# 2_cyber60-alps_matrix.net
KiCad netlist of a schematic drawn in Altium Designer
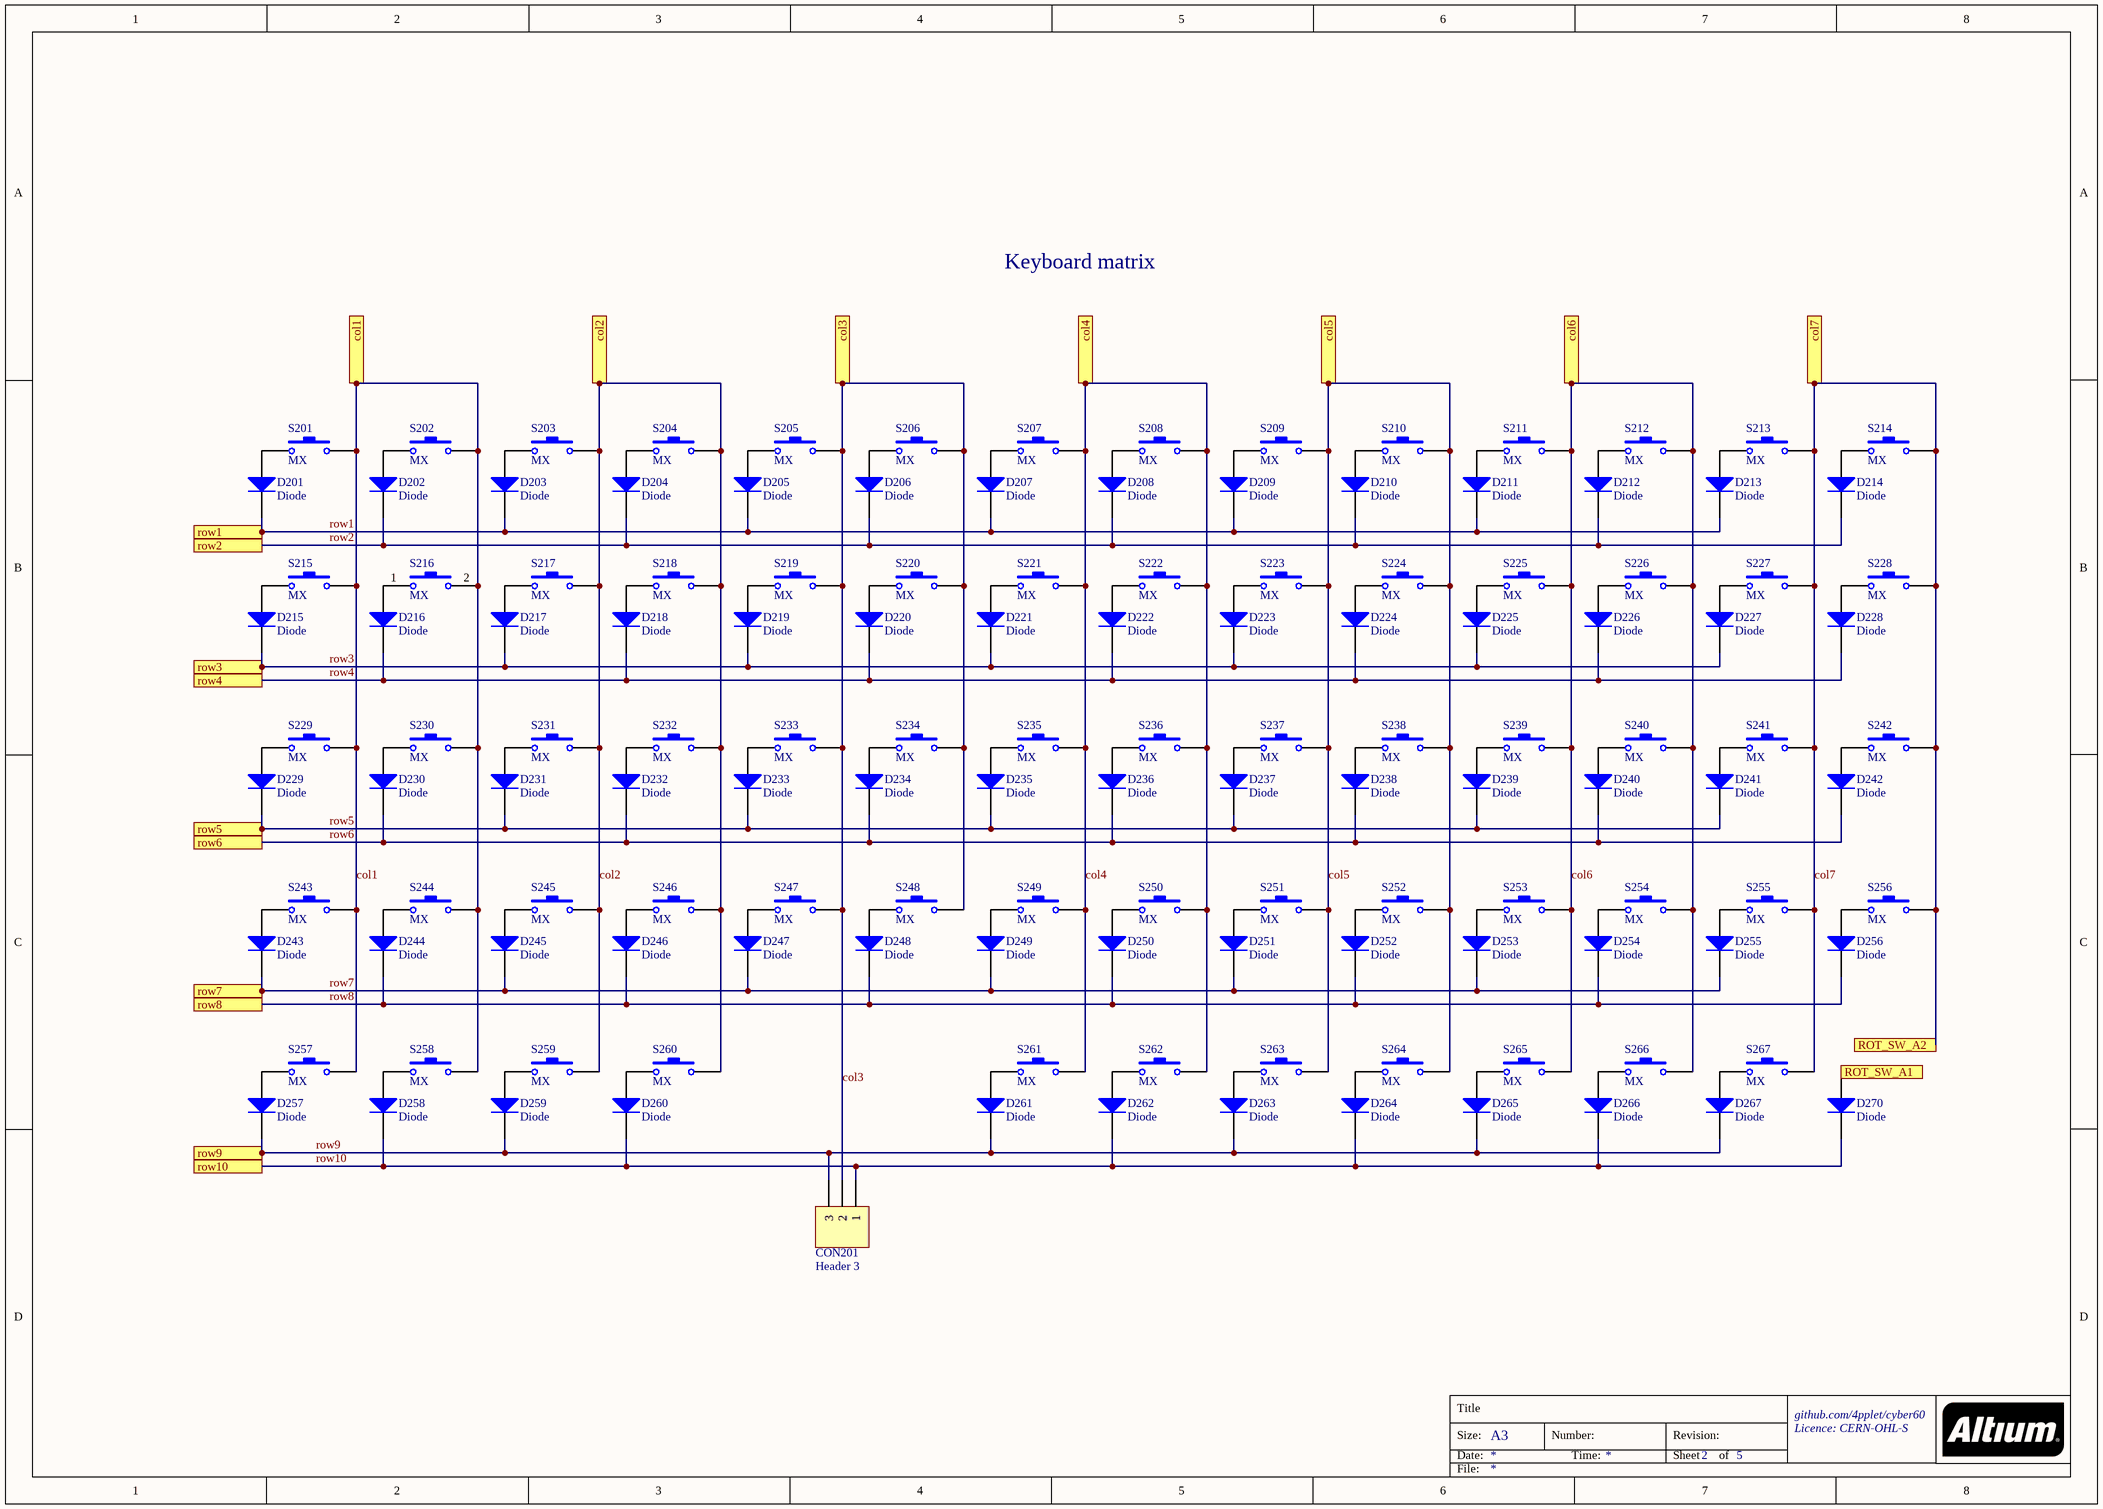
[diagram p0: 2_cyber60-alps_matrix.SchDoc]

(export (version "E")
  (design (tool "Eeschema 10.0.6"))
  (components
    (comp (ref "CON201")
      (value "Header 3")
      (footprint "HDR1X3")
      (description "Header, 3-Pin")
      (libsource (lib "Miscellaneous Connectors") (part "Header 3"))
    )
    (comp (ref "D201")
      (value "Diode")
      (footprint "SOD-123")
      (description "Default Diode")
      (fields (field (name "LCSC PART #") "C81598") (field (name "MRF.PART") "1N4148W"))
      (libsource (lib "Miscellaneous Devices") (part "Diode"))
    )
    (comp (ref "D202")
      (value "Diode")
      (footprint "SOD-123")
      (description "Default Diode")
      (fields (field (name "LCSC PART #") "C81598") (field (name "MRF.PART") "1N4148W"))
      (libsource (lib "Miscellaneous Devices") (part "Diode"))
    )
    (comp (ref "D203")
      (value "Diode")
      (footprint "SOD-123")
      (description "Default Diode")
      (fields (field (name "LCSC PART #") "C81598") (field (name "MRF.PART") "1N4148W"))
      (libsource (lib "Miscellaneous Devices") (part "Diode"))
    )
    (comp (ref "D204")
      (value "Diode")
      (footprint "SOD-123")
      (description "Default Diode")
      (fields (field (name "LCSC PART #") "C81598") (field (name "MRF.PART") "1N4148W"))
      (libsource (lib "Miscellaneous Devices") (part "Diode"))
    )
    (comp (ref "D205")
      (value "Diode")
      (footprint "SOD-123")
      (description "Default Diode")
      (fields (field (name "LCSC PART #") "C81598") (field (name "MRF.PART") "1N4148W"))
      (libsource (lib "Miscellaneous Devices") (part "Diode"))
    )
    (comp (ref "D206")
      (value "Diode")
      (footprint "SOD-123")
      (description "Default Diode")
      (fields (field (name "LCSC PART #") "C81598") (field (name "MRF.PART") "1N4148W"))
      (libsource (lib "Miscellaneous Devices") (part "Diode"))
    )
    (comp (ref "D207")
      (value "Diode")
      (footprint "SOD-123")
      (description "Default Diode")
      (fields (field (name "LCSC PART #") "C81598") (field (name "MRF.PART") "1N4148W"))
      (libsource (lib "Miscellaneous Devices") (part "Diode"))
    )
    (comp (ref "D208")
      (value "Diode")
      (footprint "SOD-123")
      (description "Default Diode")
      (fields (field (name "LCSC PART #") "C81598") (field (name "MRF.PART") "1N4148W"))
      (libsource (lib "Miscellaneous Devices") (part "Diode"))
    )
    (comp (ref "D209")
      (value "Diode")
      (footprint "SOD-123")
      (description "Default Diode")
      (fields (field (name "LCSC PART #") "C81598") (field (name "MRF.PART") "1N4148W"))
      (libsource (lib "Miscellaneous Devices") (part "Diode"))
    )
    (comp (ref "D210")
      (value "Diode")
      (footprint "SOD-123")
      (description "Default Diode")
      (fields (field (name "LCSC PART #") "C81598") (field (name "MRF.PART") "1N4148W"))
      (libsource (lib "Miscellaneous Devices") (part "Diode"))
    )
    (comp (ref "D211")
      (value "Diode")
      (footprint "SOD-123")
      (description "Default Diode")
      (fields (field (name "LCSC PART #") "C81598") (field (name "MRF.PART") "1N4148W"))
      (libsource (lib "Miscellaneous Devices") (part "Diode"))
    )
    (comp (ref "D212")
      (value "Diode")
      (footprint "SOD-123")
      (description "Default Diode")
      (fields (field (name "LCSC PART #") "C81598") (field (name "MRF.PART") "1N4148W"))
      (libsource (lib "Miscellaneous Devices") (part "Diode"))
    )
    (comp (ref "D213")
      (value "Diode")
      (footprint "SOD-123")
      (description "Default Diode")
      (fields (field (name "LCSC PART #") "C81598") (field (name "MRF.PART") "1N4148W"))
      (libsource (lib "Miscellaneous Devices") (part "Diode"))
    )
    (comp (ref "D214")
      (value "Diode")
      (footprint "SOD-123")
      (description "Default Diode")
      (fields (field (name "LCSC PART #") "C81598") (field (name "MRF.PART") "1N4148W"))
      (libsource (lib "Miscellaneous Devices") (part "Diode"))
    )
    (comp (ref "D215")
      (value "Diode")
      (footprint "SOD-123")
      (description "Default Diode")
      (fields (field (name "LCSC PART #") "C81598") (field (name "MRF.PART") "1N4148W"))
      (libsource (lib "Miscellaneous Devices") (part "Diode"))
    )
    (comp (ref "D216")
      (value "Diode")
      (footprint "SOD-123")
      (description "Default Diode")
      (fields (field (name "LCSC PART #") "C81598") (field (name "MRF.PART") "1N4148W"))
      (libsource (lib "Miscellaneous Devices") (part "Diode"))
    )
    (comp (ref "D217")
      (value "Diode")
      (footprint "SOD-123")
      (description "Default Diode")
      (fields (field (name "LCSC PART #") "C81598") (field (name "MRF.PART") "1N4148W"))
      (libsource (lib "Miscellaneous Devices") (part "Diode"))
    )
    (comp (ref "D218")
      (value "Diode")
      (footprint "SOD-123")
      (description "Default Diode")
      (fields (field (name "LCSC PART #") "C81598") (field (name "MRF.PART") "1N4148W"))
      (libsource (lib "Miscellaneous Devices") (part "Diode"))
    )
    (comp (ref "D219")
      (value "Diode")
      (footprint "SOD-123")
      (description "Default Diode")
      (fields (field (name "LCSC PART #") "C81598") (field (name "MRF.PART") "1N4148W"))
      (libsource (lib "Miscellaneous Devices") (part "Diode"))
    )
    (comp (ref "D220")
      (value "Diode")
      (footprint "SOD-123")
      (description "Default Diode")
      (fields (field (name "LCSC PART #") "C81598") (field (name "MRF.PART") "1N4148W"))
      (libsource (lib "Miscellaneous Devices") (part "Diode"))
    )
    (comp (ref "D221")
      (value "Diode")
      (footprint "SOD-123")
      (description "Default Diode")
      (fields (field (name "LCSC PART #") "C81598") (field (name "MRF.PART") "1N4148W"))
      (libsource (lib "Miscellaneous Devices") (part "Diode"))
    )
    (comp (ref "D222")
      (value "Diode")
      (footprint "SOD-123")
      (description "Default Diode")
      (fields (field (name "LCSC PART #") "C81598") (field (name "MRF.PART") "1N4148W"))
      (libsource (lib "Miscellaneous Devices") (part "Diode"))
    )
    (comp (ref "D223")
      (value "Diode")
      (footprint "SOD-123")
      (description "Default Diode")
      (fields (field (name "LCSC PART #") "C81598") (field (name "MRF.PART") "1N4148W"))
      (libsource (lib "Miscellaneous Devices") (part "Diode"))
    )
    (comp (ref "D224")
      (value "Diode")
      (footprint "SOD-123")
      (description "Default Diode")
      (fields (field (name "LCSC PART #") "C81598") (field (name "MRF.PART") "1N4148W"))
      (libsource (lib "Miscellaneous Devices") (part "Diode"))
    )
    (comp (ref "D225")
      (value "Diode")
      (footprint "SOD-123")
      (description "Default Diode")
      (fields (field (name "LCSC PART #") "C81598") (field (name "MRF.PART") "1N4148W"))
      (libsource (lib "Miscellaneous Devices") (part "Diode"))
    )
    (comp (ref "D226")
      (value "Diode")
      (footprint "SOD-123")
      (description "Default Diode")
      (fields (field (name "LCSC PART #") "C81598") (field (name "MRF.PART") "1N4148W"))
      (libsource (lib "Miscellaneous Devices") (part "Diode"))
    )
    (comp (ref "D227")
      (value "Diode")
      (footprint "SOD-123")
      (description "Default Diode")
      (fields (field (name "LCSC PART #") "C81598") (field (name "MRF.PART") "1N4148W"))
      (libsource (lib "Miscellaneous Devices") (part "Diode"))
    )
    (comp (ref "D228")
      (value "Diode")
      (footprint "SOD-123")
      (description "Default Diode")
      (fields (field (name "LCSC PART #") "C81598") (field (name "MRF.PART") "1N4148W"))
      (libsource (lib "Miscellaneous Devices") (part "Diode"))
    )
    (comp (ref "D229")
      (value "Diode")
      (footprint "SOD-123")
      (description "Default Diode")
      (fields (field (name "LCSC PART #") "C81598") (field (name "MRF.PART") "1N4148W"))
      (libsource (lib "Miscellaneous Devices") (part "Diode"))
    )
    (comp (ref "D230")
      (value "Diode")
      (footprint "SOD-123")
      (description "Default Diode")
      (fields (field (name "LCSC PART #") "C81598") (field (name "MRF.PART") "1N4148W"))
      (libsource (lib "Miscellaneous Devices") (part "Diode"))
    )
    (comp (ref "D231")
      (value "Diode")
      (footprint "SOD-123")
      (description "Default Diode")
      (fields (field (name "LCSC PART #") "C81598") (field (name "MRF.PART") "1N4148W"))
      (libsource (lib "Miscellaneous Devices") (part "Diode"))
    )
    (comp (ref "D232")
      (value "Diode")
      (footprint "SOD-123")
      (description "Default Diode")
      (fields (field (name "LCSC PART #") "C81598") (field (name "MRF.PART") "1N4148W"))
      (libsource (lib "Miscellaneous Devices") (part "Diode"))
    )
    (comp (ref "D233")
      (value "Diode")
      (footprint "SOD-123")
      (description "Default Diode")
      (fields (field (name "LCSC PART #") "C81598") (field (name "MRF.PART") "1N4148W"))
      (libsource (lib "Miscellaneous Devices") (part "Diode"))
    )
    (comp (ref "D234")
      (value "Diode")
      (footprint "SOD-123")
      (description "Default Diode")
      (fields (field (name "LCSC PART #") "C81598") (field (name "MRF.PART") "1N4148W"))
      (libsource (lib "Miscellaneous Devices") (part "Diode"))
    )
    (comp (ref "D235")
      (value "Diode")
      (footprint "SOD-123")
      (description "Default Diode")
      (fields (field (name "LCSC PART #") "C81598") (field (name "MRF.PART") "1N4148W"))
      (libsource (lib "Miscellaneous Devices") (part "Diode"))
    )
    (comp (ref "D236")
      (value "Diode")
      (footprint "SOD-123")
      (description "Default Diode")
      (fields (field (name "LCSC PART #") "C81598") (field (name "MRF.PART") "1N4148W"))
      (libsource (lib "Miscellaneous Devices") (part "Diode"))
    )
    (comp (ref "D237")
      (value "Diode")
      (footprint "SOD-123")
      (description "Default Diode")
      (fields (field (name "LCSC PART #") "C81598") (field (name "MRF.PART") "1N4148W"))
      (libsource (lib "Miscellaneous Devices") (part "Diode"))
    )
    (comp (ref "D238")
      (value "Diode")
      (footprint "SOD-123")
      (description "Default Diode")
      (fields (field (name "LCSC PART #") "C81598") (field (name "MRF.PART") "1N4148W"))
      (libsource (lib "Miscellaneous Devices") (part "Diode"))
    )
    (comp (ref "D239")
      (value "Diode")
      (footprint "SOD-123")
      (description "Default Diode")
      (fields (field (name "LCSC PART #") "C81598") (field (name "MRF.PART") "1N4148W"))
      (libsource (lib "Miscellaneous Devices") (part "Diode"))
    )
    (comp (ref "D240")
      (value "Diode")
      (footprint "SOD-123")
      (description "Default Diode")
      (fields (field (name "LCSC PART #") "C81598") (field (name "MRF.PART") "1N4148W"))
      (libsource (lib "Miscellaneous Devices") (part "Diode"))
    )
    (comp (ref "D241")
      (value "Diode")
      (footprint "SOD-123")
      (description "Default Diode")
      (fields (field (name "LCSC PART #") "C81598") (field (name "MRF.PART") "1N4148W"))
      (libsource (lib "Miscellaneous Devices") (part "Diode"))
    )
    (comp (ref "D242")
      (value "Diode")
      (footprint "SOD-123")
      (description "Default Diode")
      (fields (field (name "LCSC PART #") "C81598") (field (name "MRF.PART") "1N4148W"))
      (libsource (lib "Miscellaneous Devices") (part "Diode"))
    )
    (comp (ref "D243")
      (value "Diode")
      (footprint "SOD-123")
      (description "Default Diode")
      (fields (field (name "LCSC PART #") "C81598") (field (name "MRF.PART") "1N4148W"))
      (libsource (lib "Miscellaneous Devices") (part "Diode"))
    )
    (comp (ref "D244")
      (value "Diode")
      (footprint "SOD-123")
      (description "Default Diode")
      (fields (field (name "LCSC PART #") "C81598") (field (name "MRF.PART") "1N4148W"))
      (libsource (lib "Miscellaneous Devices") (part "Diode"))
    )
    (comp (ref "D245")
      (value "Diode")
      (footprint "SOD-123")
      (description "Default Diode")
      (fields (field (name "LCSC PART #") "C81598") (field (name "MRF.PART") "1N4148W"))
      (libsource (lib "Miscellaneous Devices") (part "Diode"))
    )
    (comp (ref "D246")
      (value "Diode")
      (footprint "SOD-123")
      (description "Default Diode")
      (fields (field (name "LCSC PART #") "C81598") (field (name "MRF.PART") "1N4148W"))
      (libsource (lib "Miscellaneous Devices") (part "Diode"))
    )
    (comp (ref "D247")
      (value "Diode")
      (footprint "SOD-123")
      (description "Default Diode")
      (fields (field (name "LCSC PART #") "C81598") (field (name "MRF.PART") "1N4148W"))
      (libsource (lib "Miscellaneous Devices") (part "Diode"))
    )
    (comp (ref "D248")
      (value "Diode")
      (footprint "SOD-123")
      (description "Default Diode")
      (fields (field (name "LCSC PART #") "C81598") (field (name "MRF.PART") "1N4148W"))
      (libsource (lib "Miscellaneous Devices") (part "Diode"))
    )
    (comp (ref "D249")
      (value "Diode")
      (footprint "SOD-123")
      (description "Default Diode")
      (fields (field (name "LCSC PART #") "C81598") (field (name "MRF.PART") "1N4148W"))
      (libsource (lib "Miscellaneous Devices") (part "Diode"))
    )
    (comp (ref "D250")
      (value "Diode")
      (footprint "SOD-123")
      (description "Default Diode")
      (fields (field (name "LCSC PART #") "C81598") (field (name "MRF.PART") "1N4148W"))
      (libsource (lib "Miscellaneous Devices") (part "Diode"))
    )
    (comp (ref "D251")
      (value "Diode")
      (footprint "SOD-123")
      (description "Default Diode")
      (fields (field (name "LCSC PART #") "C81598") (field (name "MRF.PART") "1N4148W"))
      (libsource (lib "Miscellaneous Devices") (part "Diode"))
    )
    (comp (ref "D252")
      (value "Diode")
      (footprint "SOD-123")
      (description "Default Diode")
      (fields (field (name "LCSC PART #") "C81598") (field (name "MRF.PART") "1N4148W"))
      (libsource (lib "Miscellaneous Devices") (part "Diode"))
    )
    (comp (ref "D253")
      (value "Diode")
      (footprint "SOD-123")
      (description "Default Diode")
      (fields (field (name "LCSC PART #") "C81598") (field (name "MRF.PART") "1N4148W"))
      (libsource (lib "Miscellaneous Devices") (part "Diode"))
    )
    (comp (ref "D254")
      (value "Diode")
      (footprint "SOD-123")
      (description "Default Diode")
      (fields (field (name "LCSC PART #") "C81598") (field (name "MRF.PART") "1N4148W"))
      (libsource (lib "Miscellaneous Devices") (part "Diode"))
    )
    (comp (ref "D255")
      (value "Diode")
      (footprint "SOD-123")
      (description "Default Diode")
      (fields (field (name "LCSC PART #") "C81598") (field (name "MRF.PART") "1N4148W"))
      (libsource (lib "Miscellaneous Devices") (part "Diode"))
    )
    (comp (ref "D256")
      (value "Diode")
      (footprint "SOD-123")
      (description "Default Diode")
      (fields (field (name "LCSC PART #") "C81598") (field (name "MRF.PART") "1N4148W"))
      (libsource (lib "Miscellaneous Devices") (part "Diode"))
    )
    (comp (ref "D257")
      (value "Diode")
      (footprint "SOD-123")
      (description "Default Diode")
      (fields (field (name "LCSC PART #") "C81598") (field (name "MRF.PART") "1N4148W"))
      (libsource (lib "Miscellaneous Devices") (part "Diode"))
    )
    (comp (ref "D258")
      (value "Diode")
      (footprint "SOD-123")
      (description "Default Diode")
      (fields (field (name "LCSC PART #") "C81598") (field (name "MRF.PART") "1N4148W"))
      (libsource (lib "Miscellaneous Devices") (part "Diode"))
    )
    (comp (ref "D259")
      (value "Diode")
      (footprint "SOD-123")
      (description "Default Diode")
      (fields (field (name "LCSC PART #") "C81598") (field (name "MRF.PART") "1N4148W"))
      (libsource (lib "Miscellaneous Devices") (part "Diode"))
    )
    (comp (ref "D260")
      (value "Diode")
      (footprint "SOD-123")
      (description "Default Diode")
      (fields (field (name "LCSC PART #") "C81598") (field (name "MRF.PART") "1N4148W"))
      (libsource (lib "Miscellaneous Devices") (part "Diode"))
    )
    (comp (ref "D261")
      (value "Diode")
      (footprint "SOD-123")
      (description "Default Diode")
      (fields (field (name "LCSC PART #") "C81598") (field (name "MRF.PART") "1N4148W"))
      (libsource (lib "Miscellaneous Devices") (part "Diode"))
    )
    (comp (ref "D262")
      (value "Diode")
      (footprint "SOD-123")
      (description "Default Diode")
      (fields (field (name "LCSC PART #") "C81598") (field (name "MRF.PART") "1N4148W"))
      (libsource (lib "Miscellaneous Devices") (part "Diode"))
    )
    (comp (ref "D263")
      (value "Diode")
      (footprint "SOD-123")
      (description "Default Diode")
      (fields (field (name "LCSC PART #") "C81598") (field (name "MRF.PART") "1N4148W"))
      (libsource (lib "Miscellaneous Devices") (part "Diode"))
    )
    (comp (ref "D264")
      (value "Diode")
      (footprint "SOD-123")
      (description "Default Diode")
      (fields (field (name "LCSC PART #") "C81598") (field (name "MRF.PART") "1N4148W"))
      (libsource (lib "Miscellaneous Devices") (part "Diode"))
    )
    (comp (ref "D265")
      (value "Diode")
      (footprint "SOD-123")
      (description "Default Diode")
      (fields (field (name "LCSC PART #") "C81598") (field (name "MRF.PART") "1N4148W"))
      (libsource (lib "Miscellaneous Devices") (part "Diode"))
    )
    (comp (ref "D266")
      (value "Diode")
      (footprint "SOD-123")
      (description "Default Diode")
      (fields (field (name "LCSC PART #") "C81598") (field (name "MRF.PART") "1N4148W"))
      (libsource (lib "Miscellaneous Devices") (part "Diode"))
    )
    (comp (ref "D267")
      (value "Diode")
      (footprint "SOD-123")
      (description "Default Diode")
      (fields (field (name "LCSC PART #") "C81598") (field (name "MRF.PART") "1N4148W"))
      (libsource (lib "Miscellaneous Devices") (part "Diode"))
    )
    (comp (ref "D270")
      (value "Diode")
      (footprint "SOD-123")
      (description "Default Diode")
      (fields (field (name "LCSC PART #") "C81598") (field (name "MRF.PART") "1N4148W"))
      (libsource (lib "Miscellaneous Devices") (part "Diode"))
    )
    (comp (ref "S201")
      (value "MX")
      (footprint "Alps-switch")
      (description "Switch")
      (libsource (lib "Miscellaneous Devices") (part "SW-PB"))
    )
    (comp (ref "S202")
      (value "MX")
      (footprint "Alps-switch - switched pol")
      (description "Switch")
      (libsource (lib "Miscellaneous Devices") (part "SW-PB"))
    )
    (comp (ref "S203")
      (value "MX")
      (footprint "Alps-switch - switched pol")
      (description "Switch")
      (libsource (lib "Miscellaneous Devices") (part "SW-PB"))
    )
    (comp (ref "S204")
      (value "MX")
      (footprint "Alps-switch")
      (description "Switch")
      (libsource (lib "Miscellaneous Devices") (part "SW-PB"))
    )
    (comp (ref "S205")
      (value "MX")
      (footprint "Alps-switch - switched pol")
      (description "Switch")
      (libsource (lib "Miscellaneous Devices") (part "SW-PB"))
    )
    (comp (ref "S206")
      (value "MX")
      (footprint "Alps-switch - switched pol")
      (description "Switch")
      (libsource (lib "Miscellaneous Devices") (part "SW-PB"))
    )
    (comp (ref "S207")
      (value "MX")
      (footprint "Alps-switch - switched pol")
      (description "Switch")
      (libsource (lib "Miscellaneous Devices") (part "SW-PB"))
    )
    (comp (ref "S208")
      (value "MX")
      (footprint "Alps-switch - switched pol")
      (description "Switch")
      (libsource (lib "Miscellaneous Devices") (part "SW-PB"))
    )
    (comp (ref "S209")
      (value "MX")
      (footprint "Alps-switch - switched pol")
      (description "Switch")
      (libsource (lib "Miscellaneous Devices") (part "SW-PB"))
    )
    (comp (ref "S210")
      (value "MX")
      (footprint "Alps-switch - switched pol")
      (description "Switch")
      (libsource (lib "Miscellaneous Devices") (part "SW-PB"))
    )
    (comp (ref "S211")
      (value "MX")
      (footprint "Alps-switch")
      (description "Switch")
      (libsource (lib "Miscellaneous Devices") (part "SW-PB"))
    )
    (comp (ref "S212")
      (value "MX")
      (footprint "Alps-switch - switched pol")
      (description "Switch")
      (libsource (lib "Miscellaneous Devices") (part "SW-PB"))
    )
    (comp (ref "S213")
      (value "MX")
      (footprint "Alps-switch")
      (description "Switch")
      (libsource (lib "Miscellaneous Devices") (part "SW-PB"))
    )
    (comp (ref "S214")
      (value "MX")
      (footprint "Alps-switch")
      (description "Switch")
      (libsource (lib "Miscellaneous Devices") (part "SW-PB"))
    )
    (comp (ref "S215")
      (value "MX")
      (footprint "ALPS-switch - 1.5U")
      (description "TAB")
      (libsource (lib "Miscellaneous Devices") (part "SW-PB"))
    )
    (comp (ref "S216")
      (value "MX")
      (footprint "Alps-switch - switched pol")
      (description "Switch")
      (libsource (lib "") (part "SW-PB_1"))
    )
    (comp (ref "S217")
      (value "MX")
      (footprint "Alps-switch - switched pol")
      (description "Switch")
      (libsource (lib "Miscellaneous Devices") (part "SW-PB"))
    )
    (comp (ref "S218")
      (value "MX")
      (footprint "Alps-switch - switched pol")
      (description "Switch")
      (libsource (lib "Miscellaneous Devices") (part "SW-PB"))
    )
    (comp (ref "S219")
      (value "MX")
      (footprint "Alps-switch - switched pol")
      (description "Switch")
      (libsource (lib "Miscellaneous Devices") (part "SW-PB"))
    )
    (comp (ref "S220")
      (value "MX")
      (footprint "Alps-switch")
      (description "Switch")
      (libsource (lib "Miscellaneous Devices") (part "SW-PB"))
    )
    (comp (ref "S221")
      (value "MX")
      (footprint "Alps-switch - switched pol")
      (description "Switch")
      (libsource (lib "Miscellaneous Devices") (part "SW-PB"))
    )
    (comp (ref "S222")
      (value "MX")
      (footprint "Alps-switch - switched pol")
      (description "Switch")
      (libsource (lib "Miscellaneous Devices") (part "SW-PB"))
    )
    (comp (ref "S223")
      (value "MX")
      (footprint "Alps-switch - switched pol")
      (description "Switch")
      (libsource (lib "Miscellaneous Devices") (part "SW-PB"))
    )
    (comp (ref "S224")
      (value "MX")
      (footprint "Alps-switch - switched pol")
      (description "Switch")
      (libsource (lib "Miscellaneous Devices") (part "SW-PB"))
    )
    (comp (ref "S225")
      (value "MX")
      (footprint "Alps-switch - switched pol")
      (description "Switch")
      (libsource (lib "Miscellaneous Devices") (part "SW-PB"))
    )
    (comp (ref "S226")
      (value "MX")
      (footprint "Alps-switch")
      (description "Switch")
      (libsource (lib "Miscellaneous Devices") (part "SW-PB"))
    )
    (comp (ref "S227")
      (value "MX")
      (footprint "Alps-switch")
      (description "Switch")
      (libsource (lib "Miscellaneous Devices") (part "SW-PB"))
    )
    (comp (ref "S228")
      (value "MX")
      (footprint "ALPS-switch - backspace")
      (description "Switch")
      (libsource (lib "Miscellaneous Devices") (part "SW-PB"))
    )
    (comp (ref "S229")
      (value "MX")
      (footprint "ALPS-switch - CAPS")
      (description "Switch")
      (libsource (lib "Miscellaneous Devices") (part "SW-PB"))
    )
    (comp (ref "S230")
      (value "MX")
      (footprint "Alps-switch - switched pol")
      (description "Switch")
      (libsource (lib "Miscellaneous Devices") (part "SW-PB"))
    )
    (comp (ref "S231")
      (value "MX")
      (footprint "Alps-switch - switched pol")
      (description "Switch")
      (libsource (lib "Miscellaneous Devices") (part "SW-PB"))
    )
    (comp (ref "S232")
      (value "MX")
      (footprint "Alps-switch - switched pol")
      (description "Switch")
      (libsource (lib "Miscellaneous Devices") (part "SW-PB"))
    )
    (comp (ref "S233")
      (value "MX")
      (footprint "Alps-switch - switched pol")
      (description "Switch")
      (libsource (lib "Miscellaneous Devices") (part "SW-PB"))
    )
    (comp (ref "S234")
      (value "MX")
      (footprint "Alps-switch")
      (description "Switch")
      (libsource (lib "Miscellaneous Devices") (part "SW-PB"))
    )
    (comp (ref "S235")
      (value "MX")
      (footprint "Alps-switch - switched pol")
      (description "Switch")
      (libsource (lib "Miscellaneous Devices") (part "SW-PB"))
    )
    (comp (ref "S236")
      (value "MX")
      (footprint "Alps-switch - switched pol")
      (description "Switch")
      (libsource (lib "Miscellaneous Devices") (part "SW-PB"))
    )
    (comp (ref "S237")
      (value "MX")
      (footprint "Alps-switch - switched pol")
      (description "Switch")
      (libsource (lib "Miscellaneous Devices") (part "SW-PB"))
    )
    (comp (ref "S238")
      (value "MX")
      (footprint "Alps-switch - switched pol")
      (description "Switch")
      (libsource (lib "Miscellaneous Devices") (part "SW-PB"))
    )
    (comp (ref "S239")
      (value "MX")
      (footprint "Alps-switch")
      (description "Switch")
      (libsource (lib "Miscellaneous Devices") (part "SW-PB"))
    )
    (comp (ref "S240")
      (value "MX")
      (footprint "Alps-switch - switched pol")
      (description "Switch")
      (libsource (lib "Miscellaneous Devices") (part "SW-PB"))
    )
    (comp (ref "S241")
      (value "MX")
      (footprint "Alps-switch")
      (description "Switch")
      (libsource (lib "Miscellaneous Devices") (part "SW-PB"))
    )
    (comp (ref "S242")
      (value "MX")
      (footprint "ALPS-switch - 1.5U")
      (description "Switch")
      (libsource (lib "Miscellaneous Devices") (part "SW-PB"))
    )
    (comp (ref "S243")
      (value "MX")
      (footprint "ALPS-switch - Left shift v2")
      (description "Switch")
      (libsource (lib "Miscellaneous Devices") (part "SW-PB"))
    )
    (comp (ref "S244")
      (value "MX")
      (footprint "Alps-switch - switched pol")
      (description "Switch")
      (libsource (lib "Miscellaneous Devices") (part "SW-PB"))
    )
    (comp (ref "S245")
      (value "MX")
      (footprint "Alps-switch - switched pol")
      (description "Switch")
      (libsource (lib "Miscellaneous Devices") (part "SW-PB"))
    )
    (comp (ref "S246")
      (value "MX")
      (footprint "Alps-switch - switched pol")
      (description "Switch")
      (libsource (lib "Miscellaneous Devices") (part "SW-PB"))
    )
    (comp (ref "S247")
      (value "MX")
      (footprint "Alps-switch - switched pol")
      (description "Switch")
      (libsource (lib "Miscellaneous Devices") (part "SW-PB"))
    )
    (comp (ref "S248")
      (value "MX")
      (footprint "Alps-switch")
      (description "Switch")
      (libsource (lib "Miscellaneous Devices") (part "SW-PB"))
    )
    (comp (ref "S249")
      (value "MX")
      (footprint "Alps-switch - switched pol")
      (description "Switch")
      (libsource (lib "Miscellaneous Devices") (part "SW-PB"))
    )
    (comp (ref "S250")
      (value "MX")
      (footprint "Alps-switch - switched pol")
      (description "Switch")
      (libsource (lib "Miscellaneous Devices") (part "SW-PB"))
    )
    (comp (ref "S251")
      (value "MX")
      (footprint "Alps-switch - switched pol")
      (description "Switch")
      (libsource (lib "Miscellaneous Devices") (part "SW-PB"))
    )
    (comp (ref "S252")
      (value "MX")
      (footprint "Alps-switch - switched pol")
      (description "Switch")
      (libsource (lib "Miscellaneous Devices") (part "SW-PB"))
    )
    (comp (ref "S253")
      (value "MX")
      (footprint "Alps-switch - switched pol")
      (description "Switch")
      (libsource (lib "Miscellaneous Devices") (part "SW-PB"))
    )
    (comp (ref "S254")
      (value "MX")
      (footprint "Alps-switch - switched pol")
      (description "Switch")
      (libsource (lib "Miscellaneous Devices") (part "SW-PB"))
    )
    (comp (ref "S255")
      (value "MX")
      (footprint "Alps-switch")
      (description "Switch")
      (libsource (lib "Miscellaneous Devices") (part "SW-PB"))
    )
    (comp (ref "S256")
      (value "MX")
      (footprint "ALPS-switch - Enter")
      (description "Switch")
      (libsource (lib "Miscellaneous Devices") (part "SW-PB"))
    )
    (comp (ref "S257")
      (value "MX")
      (footprint "ALPS-switch - 1.5u MOD-L")
      (description "Switch")
      (libsource (lib "Miscellaneous Devices") (part "SW-PB"))
    )
    (comp (ref "S258")
      (value "MX")
      (footprint "ALPS-switch - L_WIN - V2")
      (description "Switch")
      (libsource (lib "Miscellaneous Devices") (part "SW-PB"))
    )
    (comp (ref "S259")
      (value "MX")
      (footprint "ALPS-SWITCH - L_ALT - V2")
      (description "Switch")
      (libsource (lib "Miscellaneous Devices") (part "SW-PB"))
    )
    (comp (ref "S260")
      (value "MX")
      (footprint "ALPS-switch - L split space_V3")
      (description "Switch")
      (libsource (lib "Miscellaneous Devices") (part "SW-PB"))
    )
    (comp (ref "S261")
      (value "MX")
      (footprint "ALPS-switch - Space_V3")
      (description "Switch")
      (libsource (lib "Miscellaneous Devices") (part "SW-PB"))
    )
    (comp (ref "S262")
      (value "MX")
      (footprint "ALPS-switch - R split space_V3")
      (description "Switch")
      (libsource (lib "Miscellaneous Devices") (part "SW-PB"))
    )
    (comp (ref "S263")
      (value "MX")
      (footprint "Alps-switch - switched pol")
      (description "Switch")
      (libsource (lib "Miscellaneous Devices") (part "SW-PB"))
    )
    (comp (ref "S264")
      (value "MX")
      (footprint "ALPS-SWITCH - R_ALT - V2")
      (description "Switch")
      (libsource (lib "Miscellaneous Devices") (part "SW-PB"))
    )
    (comp (ref "S265")
      (value "MX")
      (footprint "ALPS-switch - R_WIN V2")
      (description "Switch")
      (libsource (lib "Miscellaneous Devices") (part "SW-PB"))
    )
    (comp (ref "S266")
      (value "MX")
      (footprint "ALPS-switch - 1.5u MOD-R")
      (description "Switch")
      (libsource (lib "Miscellaneous Devices") (part "SW-PB"))
    )
    (comp (ref "S267")
      (value "MX")
      (footprint "ALPS-switch - right shift - stabs")
      (description "Switch")
      (libsource (lib "Miscellaneous Devices") (part "SW-PB"))
    )
  )
  (nets
    (net (code "1") (name "/ROT_SW_A1") (class "Default")
      (node (ref "D270") (pin "1") (pinfunction "A_1") (pintype "passive"))
    )
    (net (code "2") (name "/col1") (class "Default")
      (node (ref "S201") (pin "1") (pinfunction "1_1") (pintype "passive"))
      (node (ref "S202") (pin "2") (pinfunction "2_2") (pintype "passive"))
      (node (ref "S215") (pin "1") (pinfunction "1_1") (pintype "passive"))
      (node (ref "S216") (pin "2") (pinfunction "2_2") (pintype "passive"))
      (node (ref "S229") (pin "2") (pinfunction "2_2") (pintype "passive"))
      (node (ref "S230") (pin "2") (pinfunction "2_2") (pintype "passive"))
      (node (ref "S243") (pin "1") (pinfunction "1_1") (pintype "passive"))
      (node (ref "S244") (pin "2") (pinfunction "2_2") (pintype "passive"))
      (node (ref "S257") (pin "1") (pinfunction "1_1") (pintype "passive"))
      (node (ref "S258") (pin "2") (pinfunction "2_2") (pintype "passive"))
    )
    (net (code "3") (name "/col2") (class "Default")
      (node (ref "S203") (pin "2") (pinfunction "2_2") (pintype "passive"))
      (node (ref "S204") (pin "2") (pinfunction "2_2") (pintype "passive"))
      (node (ref "S217") (pin "2") (pinfunction "2_2") (pintype "passive"))
      (node (ref "S218") (pin "2") (pinfunction "2_2") (pintype "passive"))
      (node (ref "S231") (pin "2") (pinfunction "2_2") (pintype "passive"))
      (node (ref "S232") (pin "2") (pinfunction "2_2") (pintype "passive"))
      (node (ref "S245") (pin "2") (pinfunction "2_2") (pintype "passive"))
      (node (ref "S246") (pin "2") (pinfunction "2_2") (pintype "passive"))
      (node (ref "S259") (pin "2") (pinfunction "2_2") (pintype "passive"))
      (node (ref "S260") (pin "2") (pinfunction "2_2") (pintype "passive"))
    )
    (net (code "4") (name "/col3") (class "Default")
      (node (ref "CON201") (pin "2") (pinfunction "2_2") (pintype "passive"))
      (node (ref "S205") (pin "2") (pinfunction "2_2") (pintype "passive"))
      (node (ref "S206") (pin "2") (pinfunction "2_2") (pintype "passive"))
      (node (ref "S219") (pin "2") (pinfunction "2_2") (pintype "passive"))
      (node (ref "S220") (pin "2") (pinfunction "2_2") (pintype "passive"))
      (node (ref "S233") (pin "2") (pinfunction "2_2") (pintype "passive"))
      (node (ref "S234") (pin "2") (pinfunction "2_2") (pintype "passive"))
      (node (ref "S247") (pin "2") (pinfunction "2_2") (pintype "passive"))
      (node (ref "S248") (pin "2") (pinfunction "2_2") (pintype "passive"))
    )
    (net (code "5") (name "/col4") (class "Default")
      (node (ref "S207") (pin "2") (pinfunction "2_2") (pintype "passive"))
      (node (ref "S208") (pin "2") (pinfunction "2_2") (pintype "passive"))
      (node (ref "S221") (pin "2") (pinfunction "2_2") (pintype "passive"))
      (node (ref "S222") (pin "2") (pinfunction "2_2") (pintype "passive"))
      (node (ref "S235") (pin "2") (pinfunction "2_2") (pintype "passive"))
      (node (ref "S236") (pin "2") (pinfunction "2_2") (pintype "passive"))
      (node (ref "S249") (pin "2") (pinfunction "2_2") (pintype "passive"))
      (node (ref "S250") (pin "2") (pinfunction "2_2") (pintype "passive"))
      (node (ref "S261") (pin "1") (pinfunction "1_1") (pintype "passive"))
      (node (ref "S262") (pin "2") (pinfunction "2_2") (pintype "passive"))
    )
    (net (code "6") (name "/col5") (class "Default")
      (node (ref "S209") (pin "2") (pinfunction "2_2") (pintype "passive"))
      (node (ref "S210") (pin "2") (pinfunction "2_2") (pintype "passive"))
      (node (ref "S223") (pin "2") (pinfunction "2_2") (pintype "passive"))
      (node (ref "S224") (pin "2") (pinfunction "2_2") (pintype "passive"))
      (node (ref "S237") (pin "2") (pinfunction "2_2") (pintype "passive"))
      (node (ref "S238") (pin "2") (pinfunction "2_2") (pintype "passive"))
      (node (ref "S251") (pin "2") (pinfunction "2_2") (pintype "passive"))
      (node (ref "S252") (pin "2") (pinfunction "2_2") (pintype "passive"))
      (node (ref "S263") (pin "2") (pinfunction "2_2") (pintype "passive"))
      (node (ref "S264") (pin "2") (pinfunction "2_2") (pintype "passive"))
    )
    (net (code "7") (name "/col6") (class "Default")
      (node (ref "S211") (pin "2") (pinfunction "2_2") (pintype "passive"))
      (node (ref "S212") (pin "2") (pinfunction "2_2") (pintype "passive"))
      (node (ref "S225") (pin "2") (pinfunction "2_2") (pintype "passive"))
      (node (ref "S226") (pin "2") (pinfunction "2_2") (pintype "passive"))
      (node (ref "S239") (pin "2") (pinfunction "2_2") (pintype "passive"))
      (node (ref "S240") (pin "2") (pinfunction "2_2") (pintype "passive"))
      (node (ref "S253") (pin "2") (pinfunction "2_2") (pintype "passive"))
      (node (ref "S254") (pin "2") (pinfunction "2_2") (pintype "passive"))
      (node (ref "S265") (pin "2") (pinfunction "2_2") (pintype "passive"))
      (node (ref "S266") (pin "2") (pinfunction "2_2") (pintype "passive"))
    )
    (net (code "8") (name "/col7") (class "Default")
      (node (ref "S213") (pin "2") (pinfunction "2_2") (pintype "passive"))
      (node (ref "S214") (pin "2") (pinfunction "2_2") (pintype "passive"))
      (node (ref "S227") (pin "2") (pinfunction "2_2") (pintype "passive"))
      (node (ref "S228") (pin "1") (pinfunction "1_1") (pintype "passive"))
      (node (ref "S241") (pin "2") (pinfunction "2_2") (pintype "passive"))
      (node (ref "S242") (pin "2") (pinfunction "2_2") (pintype "passive"))
      (node (ref "S255") (pin "2") (pinfunction "2_2") (pintype "passive"))
      (node (ref "S256") (pin "1") (pinfunction "1_1") (pintype "passive"))
      (node (ref "S267") (pin "2") (pinfunction "2_2") (pintype "passive"))
    )
    (net (code "9") (name "/row1") (class "Default")
      (node (ref "D201") (pin "2") (pinfunction "K_2") (pintype "passive"))
      (node (ref "D203") (pin "2") (pinfunction "K_2") (pintype "passive"))
      (node (ref "D205") (pin "2") (pinfunction "K_2") (pintype "passive"))
      (node (ref "D207") (pin "2") (pinfunction "K_2") (pintype "passive"))
      (node (ref "D209") (pin "2") (pinfunction "K_2") (pintype "passive"))
      (node (ref "D211") (pin "2") (pinfunction "K_2") (pintype "passive"))
      (node (ref "D213") (pin "2") (pinfunction "K_2") (pintype "passive"))
    )
    (net (code "10") (name "/row2") (class "Default")
      (node (ref "D202") (pin "2") (pinfunction "K_2") (pintype "passive"))
      (node (ref "D204") (pin "2") (pinfunction "K_2") (pintype "passive"))
      (node (ref "D206") (pin "2") (pinfunction "K_2") (pintype "passive"))
      (node (ref "D208") (pin "2") (pinfunction "K_2") (pintype "passive"))
      (node (ref "D210") (pin "2") (pinfunction "K_2") (pintype "passive"))
      (node (ref "D212") (pin "2") (pinfunction "K_2") (pintype "passive"))
      (node (ref "D214") (pin "2") (pinfunction "K_2") (pintype "passive"))
    )
    (net (code "11") (name "/row3") (class "Default")
      (node (ref "D215") (pin "2") (pinfunction "K_2") (pintype "passive"))
      (node (ref "D217") (pin "2") (pinfunction "K_2") (pintype "passive"))
      (node (ref "D219") (pin "2") (pinfunction "K_2") (pintype "passive"))
      (node (ref "D221") (pin "2") (pinfunction "K_2") (pintype "passive"))
      (node (ref "D223") (pin "2") (pinfunction "K_2") (pintype "passive"))
      (node (ref "D225") (pin "2") (pinfunction "K_2") (pintype "passive"))
      (node (ref "D227") (pin "2") (pinfunction "K_2") (pintype "passive"))
    )
    (net (code "12") (name "/row4") (class "Default")
      (node (ref "D216") (pin "2") (pinfunction "K_2") (pintype "passive"))
      (node (ref "D218") (pin "2") (pinfunction "K_2") (pintype "passive"))
      (node (ref "D220") (pin "2") (pinfunction "K_2") (pintype "passive"))
      (node (ref "D222") (pin "2") (pinfunction "K_2") (pintype "passive"))
      (node (ref "D224") (pin "2") (pinfunction "K_2") (pintype "passive"))
      (node (ref "D226") (pin "2") (pinfunction "K_2") (pintype "passive"))
      (node (ref "D228") (pin "2") (pinfunction "K_2") (pintype "passive"))
    )
    (net (code "13") (name "/row5") (class "Default")
      (node (ref "D229") (pin "2") (pinfunction "K_2") (pintype "passive"))
      (node (ref "D231") (pin "2") (pinfunction "K_2") (pintype "passive"))
      (node (ref "D233") (pin "2") (pinfunction "K_2") (pintype "passive"))
      (node (ref "D235") (pin "2") (pinfunction "K_2") (pintype "passive"))
      (node (ref "D237") (pin "2") (pinfunction "K_2") (pintype "passive"))
      (node (ref "D239") (pin "2") (pinfunction "K_2") (pintype "passive"))
      (node (ref "D241") (pin "2") (pinfunction "K_2") (pintype "passive"))
    )
    (net (code "14") (name "/row6") (class "Default")
      (node (ref "D230") (pin "2") (pinfunction "K_2") (pintype "passive"))
      (node (ref "D232") (pin "2") (pinfunction "K_2") (pintype "passive"))
      (node (ref "D234") (pin "2") (pinfunction "K_2") (pintype "passive"))
      (node (ref "D236") (pin "2") (pinfunction "K_2") (pintype "passive"))
      (node (ref "D238") (pin "2") (pinfunction "K_2") (pintype "passive"))
      (node (ref "D240") (pin "2") (pinfunction "K_2") (pintype "passive"))
      (node (ref "D242") (pin "2") (pinfunction "K_2") (pintype "passive"))
    )
    (net (code "15") (name "/row7") (class "Default")
      (node (ref "D243") (pin "2") (pinfunction "K_2") (pintype "passive"))
      (node (ref "D245") (pin "2") (pinfunction "K_2") (pintype "passive"))
      (node (ref "D247") (pin "2") (pinfunction "K_2") (pintype "passive"))
      (node (ref "D249") (pin "2") (pinfunction "K_2") (pintype "passive"))
      (node (ref "D251") (pin "2") (pinfunction "K_2") (pintype "passive"))
      (node (ref "D253") (pin "2") (pinfunction "K_2") (pintype "passive"))
      (node (ref "D255") (pin "2") (pinfunction "K_2") (pintype "passive"))
    )
    (net (code "16") (name "/row8") (class "Default")
      (node (ref "D244") (pin "2") (pinfunction "K_2") (pintype "passive"))
      (node (ref "D246") (pin "2") (pinfunction "K_2") (pintype "passive"))
      (node (ref "D248") (pin "2") (pinfunction "K_2") (pintype "passive"))
      (node (ref "D250") (pin "2") (pinfunction "K_2") (pintype "passive"))
      (node (ref "D252") (pin "2") (pinfunction "K_2") (pintype "passive"))
      (node (ref "D254") (pin "2") (pinfunction "K_2") (pintype "passive"))
      (node (ref "D256") (pin "2") (pinfunction "K_2") (pintype "passive"))
    )
    (net (code "17") (name "/row9") (class "Default")
      (node (ref "CON201") (pin "3") (pinfunction "3_3") (pintype "passive"))
      (node (ref "D257") (pin "2") (pinfunction "K_2") (pintype "passive"))
      (node (ref "D259") (pin "2") (pinfunction "K_2") (pintype "passive"))
      (node (ref "D261") (pin "2") (pinfunction "K_2") (pintype "passive"))
      (node (ref "D263") (pin "2") (pinfunction "K_2") (pintype "passive"))
      (node (ref "D265") (pin "2") (pinfunction "K_2") (pintype "passive"))
      (node (ref "D267") (pin "2") (pinfunction "K_2") (pintype "passive"))
    )
    (net (code "18") (name "/row10") (class "Default")
      (node (ref "CON201") (pin "1") (pinfunction "1_1") (pintype "passive"))
      (node (ref "D258") (pin "2") (pinfunction "K_2") (pintype "passive"))
      (node (ref "D260") (pin "2") (pinfunction "K_2") (pintype "passive"))
      (node (ref "D262") (pin "2") (pinfunction "K_2") (pintype "passive"))
      (node (ref "D264") (pin "2") (pinfunction "K_2") (pintype "passive"))
      (node (ref "D266") (pin "2") (pinfunction "K_2") (pintype "passive"))
      (node (ref "D270") (pin "2") (pinfunction "K_2") (pintype "passive"))
    )
    (net (code "19") (name "Net-(D201-A)") (class "Default")
      (node (ref "D201") (pin "1") (pinfunction "A_1") (pintype "passive"))
      (node (ref "S201") (pin "2") (pinfunction "2_2") (pintype "passive"))
    )
    (net (code "20") (name "Net-(D202-A)") (class "Default")
      (node (ref "D202") (pin "1") (pinfunction "A_1") (pintype "passive"))
      (node (ref "S202") (pin "1") (pinfunction "1_1") (pintype "passive"))
    )
    (net (code "21") (name "Net-(D203-A)") (class "Default")
      (node (ref "D203") (pin "1") (pinfunction "A_1") (pintype "passive"))
      (node (ref "S203") (pin "1") (pinfunction "1_1") (pintype "passive"))
    )
    (net (code "22") (name "Net-(D204-A)") (class "Default")
      (node (ref "D204") (pin "1") (pinfunction "A_1") (pintype "passive"))
      (node (ref "S204") (pin "1") (pinfunction "1_1") (pintype "passive"))
    )
    (net (code "23") (name "Net-(D205-A)") (class "Default")
      (node (ref "D205") (pin "1") (pinfunction "A_1") (pintype "passive"))
      (node (ref "S205") (pin "1") (pinfunction "1_1") (pintype "passive"))
    )
    (net (code "24") (name "Net-(D206-A)") (class "Default")
      (node (ref "D206") (pin "1") (pinfunction "A_1") (pintype "passive"))
      (node (ref "S206") (pin "1") (pinfunction "1_1") (pintype "passive"))
    )
    (net (code "25") (name "Net-(D207-A)") (class "Default")
      (node (ref "D207") (pin "1") (pinfunction "A_1") (pintype "passive"))
      (node (ref "S207") (pin "1") (pinfunction "1_1") (pintype "passive"))
    )
    (net (code "26") (name "Net-(D208-A)") (class "Default")
      (node (ref "D208") (pin "1") (pinfunction "A_1") (pintype "passive"))
      (node (ref "S208") (pin "1") (pinfunction "1_1") (pintype "passive"))
    )
    (net (code "27") (name "Net-(D209-A)") (class "Default")
      (node (ref "D209") (pin "1") (pinfunction "A_1") (pintype "passive"))
      (node (ref "S209") (pin "1") (pinfunction "1_1") (pintype "passive"))
    )
    (net (code "28") (name "Net-(D210-A)") (class "Default")
      (node (ref "D210") (pin "1") (pinfunction "A_1") (pintype "passive"))
      (node (ref "S210") (pin "1") (pinfunction "1_1") (pintype "passive"))
    )
    (net (code "29") (name "Net-(D211-A)") (class "Default")
      (node (ref "D211") (pin "1") (pinfunction "A_1") (pintype "passive"))
      (node (ref "S211") (pin "1") (pinfunction "1_1") (pintype "passive"))
    )
    (net (code "30") (name "Net-(D212-A)") (class "Default")
      (node (ref "D212") (pin "1") (pinfunction "A_1") (pintype "passive"))
      (node (ref "S212") (pin "1") (pinfunction "1_1") (pintype "passive"))
    )
    (net (code "31") (name "Net-(D213-A)") (class "Default")
      (node (ref "D213") (pin "1") (pinfunction "A_1") (pintype "passive"))
      (node (ref "S213") (pin "1") (pinfunction "1_1") (pintype "passive"))
    )
    (net (code "32") (name "Net-(D214-A)") (class "Default")
      (node (ref "D214") (pin "1") (pinfunction "A_1") (pintype "passive"))
      (node (ref "S214") (pin "1") (pinfunction "1_1") (pintype "passive"))
    )
    (net (code "33") (name "Net-(D215-A)") (class "Default")
      (node (ref "D215") (pin "1") (pinfunction "A_1") (pintype "passive"))
      (node (ref "S215") (pin "2") (pinfunction "2_2") (pintype "passive"))
    )
    (net (code "34") (name "Net-(D216-A)") (class "Default")
      (node (ref "D216") (pin "1") (pinfunction "A_1") (pintype "passive"))
      (node (ref "S216") (pin "1") (pinfunction "1_1") (pintype "passive"))
    )
    (net (code "35") (name "Net-(D217-A)") (class "Default")
      (node (ref "D217") (pin "1") (pinfunction "A_1") (pintype "passive"))
      (node (ref "S217") (pin "1") (pinfunction "1_1") (pintype "passive"))
    )
    (net (code "36") (name "Net-(D218-A)") (class "Default")
      (node (ref "D218") (pin "1") (pinfunction "A_1") (pintype "passive"))
      (node (ref "S218") (pin "1") (pinfunction "1_1") (pintype "passive"))
    )
    (net (code "37") (name "Net-(D219-A)") (class "Default")
      (node (ref "D219") (pin "1") (pinfunction "A_1") (pintype "passive"))
      (node (ref "S219") (pin "1") (pinfunction "1_1") (pintype "passive"))
    )
    (net (code "38") (name "Net-(D220-A)") (class "Default")
      (node (ref "D220") (pin "1") (pinfunction "A_1") (pintype "passive"))
      (node (ref "S220") (pin "1") (pinfunction "1_1") (pintype "passive"))
    )
    (net (code "39") (name "Net-(D221-A)") (class "Default")
      (node (ref "D221") (pin "1") (pinfunction "A_1") (pintype "passive"))
      (node (ref "S221") (pin "1") (pinfunction "1_1") (pintype "passive"))
    )
    (net (code "40") (name "Net-(D222-A)") (class "Default")
      (node (ref "D222") (pin "1") (pinfunction "A_1") (pintype "passive"))
      (node (ref "S222") (pin "1") (pinfunction "1_1") (pintype "passive"))
    )
    (net (code "41") (name "Net-(D223-A)") (class "Default")
      (node (ref "D223") (pin "1") (pinfunction "A_1") (pintype "passive"))
      (node (ref "S223") (pin "1") (pinfunction "1_1") (pintype "passive"))
    )
    (net (code "42") (name "Net-(D224-A)") (class "Default")
      (node (ref "D224") (pin "1") (pinfunction "A_1") (pintype "passive"))
      (node (ref "S224") (pin "1") (pinfunction "1_1") (pintype "passive"))
    )
    (net (code "43") (name "Net-(D225-A)") (class "Default")
      (node (ref "D225") (pin "1") (pinfunction "A_1") (pintype "passive"))
      (node (ref "S225") (pin "1") (pinfunction "1_1") (pintype "passive"))
    )
    (net (code "44") (name "Net-(D226-A)") (class "Default")
      (node (ref "D226") (pin "1") (pinfunction "A_1") (pintype "passive"))
      (node (ref "S226") (pin "1") (pinfunction "1_1") (pintype "passive"))
    )
    (net (code "45") (name "Net-(D227-A)") (class "Default")
      (node (ref "D227") (pin "1") (pinfunction "A_1") (pintype "passive"))
      (node (ref "S227") (pin "1") (pinfunction "1_1") (pintype "passive"))
    )
    (net (code "46") (name "Net-(D228-A)") (class "Default")
      (node (ref "D228") (pin "1") (pinfunction "A_1") (pintype "passive"))
      (node (ref "S228") (pin "2") (pinfunction "2_2") (pintype "passive"))
    )
    (net (code "47") (name "Net-(D229-A)") (class "Default")
      (node (ref "D229") (pin "1") (pinfunction "A_1") (pintype "passive"))
      (node (ref "S229") (pin "1") (pinfunction "1_1") (pintype "passive"))
    )
    (net (code "48") (name "Net-(D230-A)") (class "Default")
      (node (ref "D230") (pin "1") (pinfunction "A_1") (pintype "passive"))
      (node (ref "S230") (pin "1") (pinfunction "1_1") (pintype "passive"))
    )
    (net (code "49") (name "Net-(D231-A)") (class "Default")
      (node (ref "D231") (pin "1") (pinfunction "A_1") (pintype "passive"))
      (node (ref "S231") (pin "1") (pinfunction "1_1") (pintype "passive"))
    )
    (net (code "50") (name "Net-(D232-A)") (class "Default")
      (node (ref "D232") (pin "1") (pinfunction "A_1") (pintype "passive"))
      (node (ref "S232") (pin "1") (pinfunction "1_1") (pintype "passive"))
    )
    (net (code "51") (name "Net-(D233-A)") (class "Default")
      (node (ref "D233") (pin "1") (pinfunction "A_1") (pintype "passive"))
      (node (ref "S233") (pin "1") (pinfunction "1_1") (pintype "passive"))
    )
    (net (code "52") (name "Net-(D234-A)") (class "Default")
      (node (ref "D234") (pin "1") (pinfunction "A_1") (pintype "passive"))
      (node (ref "S234") (pin "1") (pinfunction "1_1") (pintype "passive"))
    )
    (net (code "53") (name "Net-(D235-A)") (class "Default")
      (node (ref "D235") (pin "1") (pinfunction "A_1") (pintype "passive"))
      (node (ref "S235") (pin "1") (pinfunction "1_1") (pintype "passive"))
    )
    (net (code "54") (name "Net-(D236-A)") (class "Default")
      (node (ref "D236") (pin "1") (pinfunction "A_1") (pintype "passive"))
      (node (ref "S236") (pin "1") (pinfunction "1_1") (pintype "passive"))
    )
    (net (code "55") (name "Net-(D237-A)") (class "Default")
      (node (ref "D237") (pin "1") (pinfunction "A_1") (pintype "passive"))
      (node (ref "S237") (pin "1") (pinfunction "1_1") (pintype "passive"))
    )
    (net (code "56") (name "Net-(D238-A)") (class "Default")
      (node (ref "D238") (pin "1") (pinfunction "A_1") (pintype "passive"))
      (node (ref "S238") (pin "1") (pinfunction "1_1") (pintype "passive"))
    )
    (net (code "57") (name "Net-(D239-A)") (class "Default")
      (node (ref "D239") (pin "1") (pinfunction "A_1") (pintype "passive"))
      (node (ref "S239") (pin "1") (pinfunction "1_1") (pintype "passive"))
    )
    (net (code "58") (name "Net-(D240-A)") (class "Default")
      (node (ref "D240") (pin "1") (pinfunction "A_1") (pintype "passive"))
      (node (ref "S240") (pin "1") (pinfunction "1_1") (pintype "passive"))
    )
    (net (code "59") (name "Net-(D241-A)") (class "Default")
      (node (ref "D241") (pin "1") (pinfunction "A_1") (pintype "passive"))
      (node (ref "S241") (pin "1") (pinfunction "1_1") (pintype "passive"))
    )
    (net (code "60") (name "Net-(D242-A)") (class "Default")
      (node (ref "D242") (pin "1") (pinfunction "A_1") (pintype "passive"))
      (node (ref "S242") (pin "1") (pinfunction "1_1") (pintype "passive"))
    )
    (net (code "61") (name "Net-(D243-A)") (class "Default")
      (node (ref "D243") (pin "1") (pinfunction "A_1") (pintype "passive"))
      (node (ref "S243") (pin "2") (pinfunction "2_2") (pintype "passive"))
    )
    (net (code "62") (name "Net-(D244-A)") (class "Default")
      (node (ref "D244") (pin "1") (pinfunction "A_1") (pintype "passive"))
      (node (ref "S244") (pin "1") (pinfunction "1_1") (pintype "passive"))
    )
    (net (code "63") (name "Net-(D245-A)") (class "Default")
      (node (ref "D245") (pin "1") (pinfunction "A_1") (pintype "passive"))
      (node (ref "S245") (pin "1") (pinfunction "1_1") (pintype "passive"))
    )
    (net (code "64") (name "Net-(D246-A)") (class "Default")
      (node (ref "D246") (pin "1") (pinfunction "A_1") (pintype "passive"))
      (node (ref "S246") (pin "1") (pinfunction "1_1") (pintype "passive"))
    )
    (net (code "65") (name "Net-(D247-A)") (class "Default")
      (node (ref "D247") (pin "1") (pinfunction "A_1") (pintype "passive"))
      (node (ref "S247") (pin "1") (pinfunction "1_1") (pintype "passive"))
    )
    (net (code "66") (name "Net-(D248-A)") (class "Default")
      (node (ref "D248") (pin "1") (pinfunction "A_1") (pintype "passive"))
      (node (ref "S248") (pin "1") (pinfunction "1_1") (pintype "passive"))
    )
    (net (code "67") (name "Net-(D249-A)") (class "Default")
      (node (ref "D249") (pin "1") (pinfunction "A_1") (pintype "passive"))
      (node (ref "S249") (pin "1") (pinfunction "1_1") (pintype "passive"))
    )
    (net (code "68") (name "Net-(D250-A)") (class "Default")
      (node (ref "D250") (pin "1") (pinfunction "A_1") (pintype "passive"))
      (node (ref "S250") (pin "1") (pinfunction "1_1") (pintype "passive"))
    )
    (net (code "69") (name "Net-(D251-A)") (class "Default")
      (node (ref "D251") (pin "1") (pinfunction "A_1") (pintype "passive"))
      (node (ref "S251") (pin "1") (pinfunction "1_1") (pintype "passive"))
    )
    (net (code "70") (name "Net-(D252-A)") (class "Default")
      (node (ref "D252") (pin "1") (pinfunction "A_1") (pintype "passive"))
      (node (ref "S252") (pin "1") (pinfunction "1_1") (pintype "passive"))
    )
    (net (code "71") (name "Net-(D253-A)") (class "Default")
      (node (ref "D253") (pin "1") (pinfunction "A_1") (pintype "passive"))
      (node (ref "S253") (pin "1") (pinfunction "1_1") (pintype "passive"))
    )
    (net (code "72") (name "Net-(D254-A)") (class "Default")
      (node (ref "D254") (pin "1") (pinfunction "A_1") (pintype "passive"))
      (node (ref "S254") (pin "1") (pinfunction "1_1") (pintype "passive"))
    )
    (net (code "73") (name "Net-(D255-A)") (class "Default")
      (node (ref "D255") (pin "1") (pinfunction "A_1") (pintype "passive"))
      (node (ref "S255") (pin "1") (pinfunction "1_1") (pintype "passive"))
    )
    (net (code "74") (name "Net-(D256-A)") (class "Default")
      (node (ref "D256") (pin "1") (pinfunction "A_1") (pintype "passive"))
      (node (ref "S256") (pin "2") (pinfunction "2_2") (pintype "passive"))
    )
    (net (code "75") (name "Net-(D257-A)") (class "Default")
      (node (ref "D257") (pin "1") (pinfunction "A_1") (pintype "passive"))
      (node (ref "S257") (pin "2") (pinfunction "2_2") (pintype "passive"))
    )
    (net (code "76") (name "Net-(D258-A)") (class "Default")
      (node (ref "D258") (pin "1") (pinfunction "A_1") (pintype "passive"))
      (node (ref "S258") (pin "1") (pinfunction "1_1") (pintype "passive"))
    )
    (net (code "77") (name "Net-(D259-A)") (class "Default")
      (node (ref "D259") (pin "1") (pinfunction "A_1") (pintype "passive"))
      (node (ref "S259") (pin "1") (pinfunction "1_1") (pintype "passive"))
    )
    (net (code "78") (name "Net-(D260-A)") (class "Default")
      (node (ref "D260") (pin "1") (pinfunction "A_1") (pintype "passive"))
      (node (ref "S260") (pin "1") (pinfunction "1_1") (pintype "passive"))
    )
    (net (code "79") (name "Net-(D261-A)") (class "Default")
      (node (ref "D261") (pin "1") (pinfunction "A_1") (pintype "passive"))
      (node (ref "S261") (pin "2") (pinfunction "2_2") (pintype "passive"))
    )
    (net (code "80") (name "Net-(D262-A)") (class "Default")
      (node (ref "D262") (pin "1") (pinfunction "A_1") (pintype "passive"))
      (node (ref "S262") (pin "1") (pinfunction "1_1") (pintype "passive"))
    )
    (net (code "81") (name "Net-(D263-A)") (class "Default")
      (node (ref "D263") (pin "1") (pinfunction "A_1") (pintype "passive"))
      (node (ref "S263") (pin "1") (pinfunction "1_1") (pintype "passive"))
    )
    (net (code "82") (name "Net-(D264-A)") (class "Default")
      (node (ref "D264") (pin "1") (pinfunction "A_1") (pintype "passive"))
      (node (ref "S264") (pin "1") (pinfunction "1_1") (pintype "passive"))
    )
    (net (code "83") (name "Net-(D265-A)") (class "Default")
      (node (ref "D265") (pin "1") (pinfunction "A_1") (pintype "passive"))
      (node (ref "S265") (pin "1") (pinfunction "1_1") (pintype "passive"))
    )
    (net (code "84") (name "Net-(D266-A)") (class "Default")
      (node (ref "D266") (pin "1") (pinfunction "A_1") (pintype "passive"))
      (node (ref "S266") (pin "1") (pinfunction "1_1") (pintype "passive"))
    )
    (net (code "85") (name "Net-(D267-A)") (class "Default")
      (node (ref "D267") (pin "1") (pinfunction "A_1") (pintype "passive"))
      (node (ref "S267") (pin "1") (pinfunction "1_1") (pintype "passive"))
    )
  )
)
